# MAX5419.net
KiCad netlist of a schematic drawn in EAGLE
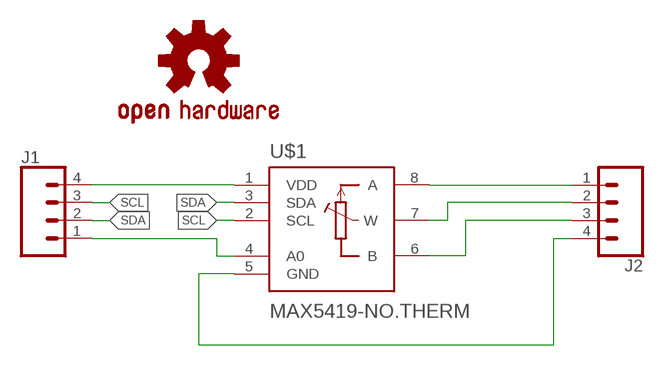
[diagram p0: schematic, sheet 1]

(export (version "E")
  (design (tool "Eeschema 10.0.6"))
  (components
    (comp (ref "J1")
      (value "CONN_041X04_NO_SILK")
      (footprint "eagle-import:1X04_NO_SILK")
      (libsource (lib "eagle-import") (part "CONN_041X04_NO_SILK"))
    )
    (comp (ref "J2")
      (value "CONN_041X04_NO_SILK")
      (footprint "eagle-import:1X04_NO_SILK")
      (libsource (lib "eagle-import") (part "CONN_041X04_NO_SILK"))
    )
    (comp (ref "LOGO1")
      (value "OSHW-LOGOS")
      (footprint "eagle-import:OSHW-LOGO-S")
      (libsource (lib "eagle-import") (part "OSHW-LOGOS"))
    )
    (comp (ref "U$1")
      (value "MAX5419-NO.THERM")
      (footprint "eagle-import:TDFN8-3X3MM")
      (libsource (lib "eagle-import") (part "MAX5419-NO.THERM"))
    )
  )
  (nets
    (net (code "1") (name "Net-(U$1-A)") (class "Default")
      (node (ref "J2") (pin "1") (pinfunction "1_1") (pintype "passive"))
      (node (ref "U$1") (pin "8") (pinfunction "A_8") (pintype "bidirectional"))
    )
    (net (code "2") (name "Net-(U$1-A0)") (class "Default")
      (node (ref "J1") (pin "1") (pinfunction "1_1") (pintype "passive"))
      (node (ref "U$1") (pin "4") (pinfunction "A0_4") (pintype "bidirectional"))
    )
    (net (code "3") (name "Net-(U$1-B)") (class "Default")
      (node (ref "J2") (pin "3") (pinfunction "3_3") (pintype "passive"))
      (node (ref "U$1") (pin "6") (pinfunction "B_6") (pintype "bidirectional"))
    )
    (net (code "4") (name "Net-(U$1-GND)") (class "Default")
      (node (ref "J2") (pin "4") (pinfunction "4_4") (pintype "passive"))
      (node (ref "U$1") (pin "5") (pinfunction "GND_5") (pintype "bidirectional"))
    )
    (net (code "5") (name "Net-(U$1-VDD)") (class "Default")
      (node (ref "J1") (pin "4") (pinfunction "4_4") (pintype "passive"))
      (node (ref "U$1") (pin "1") (pinfunction "VDD_1") (pintype "bidirectional"))
    )
    (net (code "6") (name "Net-(U$1-W)") (class "Default")
      (node (ref "J2") (pin "2") (pinfunction "2_2") (pintype "passive"))
      (node (ref "U$1") (pin "7") (pinfunction "W_7") (pintype "bidirectional"))
    )
    (net (code "7") (name "SCL") (class "Default")
      (node (ref "J1") (pin "3") (pinfunction "3_3") (pintype "passive"))
      (node (ref "U$1") (pin "2") (pinfunction "SCL_2") (pintype "bidirectional"))
    )
    (net (code "8") (name "SDA") (class "Default")
      (node (ref "J1") (pin "2") (pinfunction "2_2") (pintype "passive"))
      (node (ref "U$1") (pin "3") (pinfunction "SDA_3") (pintype "bidirectional"))
    )
  )
)
